# WeatherBoard_v1_1.net
KiCad netlist of a schematic drawn in EAGLE
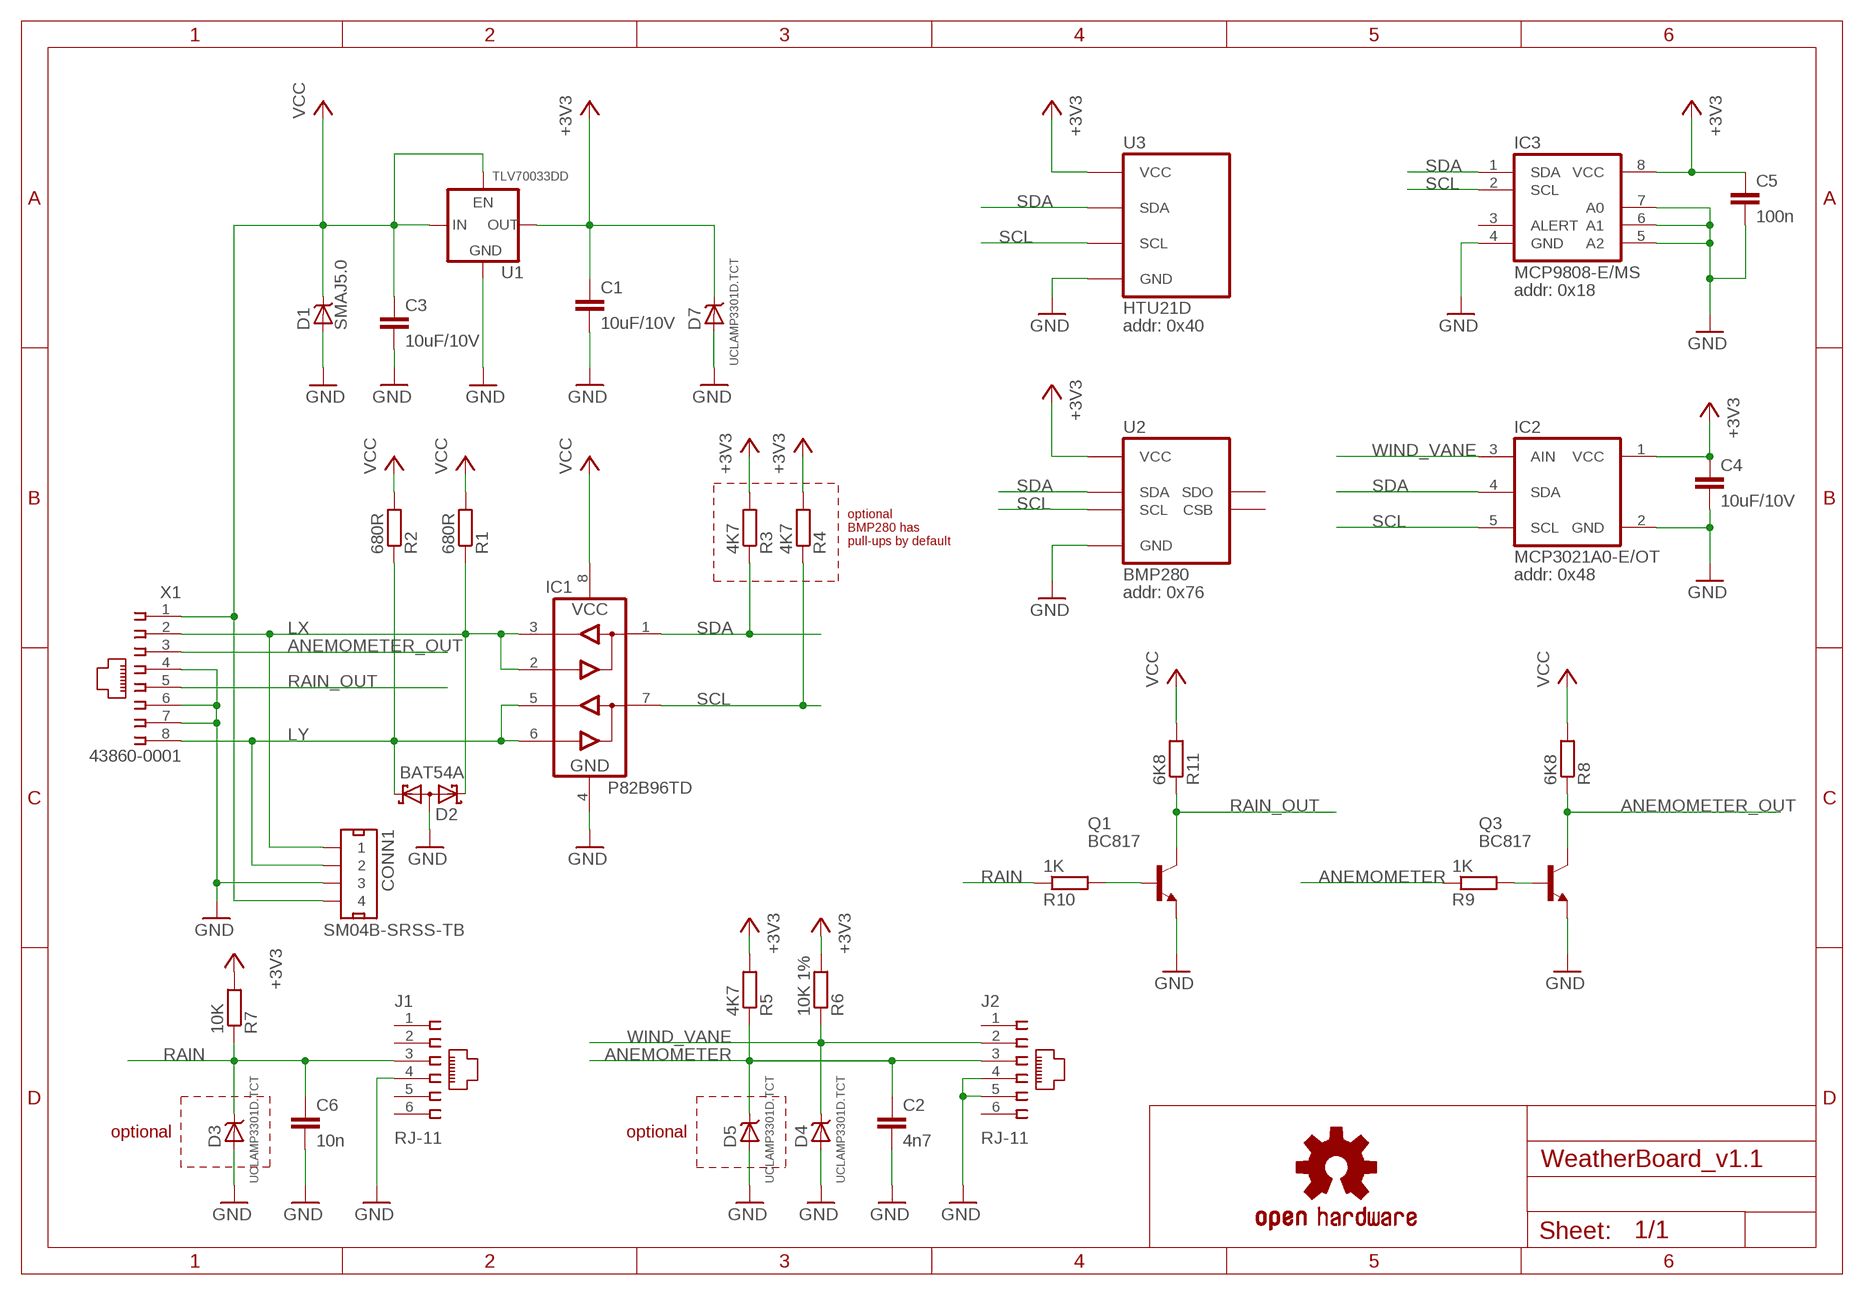
[diagram p0: schematic, sheet 1]

(export (version "E")
  (design (tool "Eeschema 10.0.6"))
  (components
    (comp (ref "C1")
      (value "10uF/10V")
      (footprint "eagle-import:C0805")
      (libsource (lib "eagle-import") (part "C-EUC0805"))
    )
    (comp (ref "C2")
      (value "4n7")
      (footprint "eagle-import:C0805")
      (libsource (lib "eagle-import") (part "C-EUC0805"))
    )
    (comp (ref "C3")
      (value "10uF/10V")
      (footprint "eagle-import:C0805")
      (libsource (lib "eagle-import") (part "C-EUC0805"))
    )
    (comp (ref "C4")
      (value "10uF/10V")
      (footprint "eagle-import:C0805")
      (libsource (lib "eagle-import") (part "C-EUC0805"))
    )
    (comp (ref "C5")
      (value "100n")
      (footprint "eagle-import:C0805")
      (libsource (lib "eagle-import") (part "C-EUC0805"))
    )
    (comp (ref "C6")
      (value "10n")
      (footprint "eagle-import:C0805")
      (libsource (lib "eagle-import") (part "C-EUC0805"))
    )
    (comp (ref "CONN1")
      (value "SM04B-SRSS-TB")
      (footprint "eagle-import:JST-SRSS-4-T")
      (libsource (lib "eagle-import") (part "?M04B-SRSS-TBS"))
    )
    (comp (ref "D1")
      (value "SMAJ5.0")
      (footprint "eagle-import:DO214AC")
      (libsource (lib "eagle-import") (part "SM?JA5.0"))
    )
    (comp (ref "D2")
      (value "BAT54A")
      (footprint "eagle-import:SOT23")
      (libsource (lib "eagle-import") (part "BAT54A"))
    )
    (comp (ref "D3")
      (value "UCLAMP3301D.TCT")
      (footprint "eagle-import:SOD323")
      (libsource (lib "eagle-import") (part "UCLAMP3301?.TCTD"))
    )
    (comp (ref "D4")
      (value "UCLAMP3301D.TCT")
      (footprint "eagle-import:SOD323")
      (libsource (lib "eagle-import") (part "UCLAMP3301?.TCTD"))
    )
    (comp (ref "D5")
      (value "UCLAMP3301D.TCT")
      (footprint "eagle-import:SOD323")
      (libsource (lib "eagle-import") (part "UCLAMP3301?.TCTD"))
    )
    (comp (ref "D7")
      (value "UCLAMP3301D.TCT")
      (footprint "eagle-import:SOD323")
      (libsource (lib "eagle-import") (part "UCLAMP3301?.TCTD"))
    )
    (comp (ref "IC1")
      (value "P82B96TD")
      (footprint "eagle-import:SO08")
      (libsource (lib "eagle-import") (part "P82B96?TD"))
    )
    (comp (ref "IC2")
      (value "MCP3021A0-E/OT")
      (footprint "eagle-import:SOT23-5")
      (libsource (lib "eagle-import") (part "MCP3021-E/?OTA0"))
    )
    (comp (ref "IC3")
      (value "MCP9808-E/MS")
      (footprint "eagle-import:MSOP8")
      (libsource (lib "eagle-import") (part "MCP9808-E/?MS"))
    )
    (comp (ref "J1")
      (value "RJ-11")
      (footprint "eagle-import:615006138421")
      (libsource (lib "eagle-import") (part "RJ-11"))
    )
    (comp (ref "J2")
      (value "RJ-11")
      (footprint "eagle-import:615006138421")
      (libsource (lib "eagle-import") (part "RJ-11"))
    )
    (comp (ref "LOGO1")
      (value "OSHW-LOGOM-COPPER")
      (footprint "eagle-import:OSHW-LOGO-M_COPPER")
      (libsource (lib "eagle-import") (part "OSHW-LOGOM-COPPER"))
    )
    (comp (ref "Q1")
      (value "BC817")
      (footprint "eagle-import:SOT23-BEC")
      (libsource (lib "eagle-import") (part "BC817SMD-40"))
    )
    (comp (ref "Q3")
      (value "BC817")
      (footprint "eagle-import:SOT23-BEC")
      (libsource (lib "eagle-import") (part "BC817SMD-40"))
    )
    (comp (ref "R1")
      (value "680R")
      (footprint "eagle-import:R0805")
      (libsource (lib "eagle-import") (part "R-EU_R0805"))
    )
    (comp (ref "R2")
      (value "680R")
      (footprint "eagle-import:R0805")
      (libsource (lib "eagle-import") (part "R-EU_R0805"))
    )
    (comp (ref "R3")
      (value "4K7")
      (footprint "eagle-import:R0805")
      (libsource (lib "eagle-import") (part "R-EU_R0805"))
    )
    (comp (ref "R4")
      (value "4K7")
      (footprint "eagle-import:R0805")
      (libsource (lib "eagle-import") (part "R-EU_R0805"))
    )
    (comp (ref "R5")
      (value "4K7")
      (footprint "eagle-import:R0805")
      (libsource (lib "eagle-import") (part "R-EU_R0805"))
    )
    (comp (ref "R6")
      (value "10K 1%")
      (footprint "eagle-import:R0805")
      (libsource (lib "eagle-import") (part "R-EU_R0805"))
    )
    (comp (ref "R7")
      (value "10K")
      (footprint "eagle-import:R0805")
      (libsource (lib "eagle-import") (part "R-EU_R0805"))
    )
    (comp (ref "R8")
      (value "6K8")
      (footprint "eagle-import:R0805")
      (libsource (lib "eagle-import") (part "R-EU_R0805"))
    )
    (comp (ref "R9")
      (value "1K")
      (footprint "eagle-import:R0805")
      (libsource (lib "eagle-import") (part "R-EU_R0805"))
    )
    (comp (ref "R10")
      (value "1K")
      (footprint "eagle-import:R0805")
      (libsource (lib "eagle-import") (part "R-EU_R0805"))
    )
    (comp (ref "R11")
      (value "6K8")
      (footprint "eagle-import:R0805")
      (libsource (lib "eagle-import") (part "R-EU_R0805"))
    )
    (comp (ref "U1")
      (value "TLV70033DD")
      (footprint "eagle-import:SOT23-5")
      (libsource (lib "eagle-import") (part "TLV700DD33"))
    )
    (comp (ref "U2")
      (value "BMP280")
      (footprint "eagle-import:BM_280")
      (libsource (lib "eagle-import") (part "BM280P"))
    )
    (comp (ref "U3")
      (value "HTU21D")
      (footprint "eagle-import:HTU21D")
      (libsource (lib "eagle-import") (part "HTU21D"))
    )
    (comp (ref "X1")
      (value "43860-0001")
      (footprint "eagle-import:MX-43860-0001")
      (libsource (lib "eagle-import") (part "43860-0001"))
    )
  )
  (nets
    (net (code "1") (name "+3V3") (class "Default")
      (node (ref "C1") (pin "1") (pinfunction "1_1") (pintype "passive"))
      (node (ref "C4") (pin "1") (pinfunction "1_1") (pintype "passive"))
      (node (ref "C5") (pin "1") (pinfunction "1_1") (pintype "passive"))
      (node (ref "D7") (pin "C") (pinfunction "C_C") (pintype "passive"))
      (node (ref "IC2") (pin "1") (pinfunction "VCC_1") (pintype "power_in"))
      (node (ref "IC3") (pin "8") (pinfunction "VCC_8") (pintype "power_in"))
      (node (ref "R3") (pin "2") (pinfunction "2_2") (pintype "passive"))
      (node (ref "R4") (pin "2") (pinfunction "2_2") (pintype "passive"))
      (node (ref "R5") (pin "2") (pinfunction "2_2") (pintype "passive"))
      (node (ref "R6") (pin "2") (pinfunction "2_2") (pintype "passive"))
      (node (ref "R7") (pin "2") (pinfunction "2_2") (pintype "passive"))
      (node (ref "U1") (pin "5") (pinfunction "VOUT_5") (pintype "power_in"))
      (node (ref "U2") (pin "VCC") (pinfunction "VCC_VCC") (pintype "power_in"))
      (node (ref "U3") (pin "VCC") (pinfunction "VCC_VCC") (pintype "power_in"))
    )
    (net (code "2") (name "/ANEMOMETER") (class "Default")
      (node (ref "C2") (pin "1") (pinfunction "1_1") (pintype "passive"))
      (node (ref "D5") (pin "C") (pinfunction "C_C") (pintype "passive"))
      (node (ref "J2") (pin "3") (pinfunction "3_3") (pintype "passive"))
      (node (ref "R5") (pin "1") (pinfunction "1_1") (pintype "passive"))
      (node (ref "R9") (pin "1") (pinfunction "1_1") (pintype "passive"))
    )
    (net (code "3") (name "/ANEMOMETER_OUT") (class "Default")
      (node (ref "Q3") (pin "C") (pinfunction "C_C") (pintype "passive"))
      (node (ref "R8") (pin "1") (pinfunction "1_1") (pintype "passive"))
      (node (ref "X1") (pin "3") (pinfunction "3_3") (pintype "passive"))
    )
    (net (code "4") (name "/LX") (class "Default")
      (node (ref "CONN1") (pin "1") (pinfunction "1_1") (pintype "passive"))
      (node (ref "D2") (pin "2") (pinfunction "K2_2") (pintype "passive"))
      (node (ref "IC1") (pin "2") (pinfunction "RX_2") (pintype "open_collector"))
      (node (ref "IC1") (pin "3") (pinfunction "TX_3") (pintype "open_collector"))
      (node (ref "R1") (pin "1") (pinfunction "1_1") (pintype "passive"))
      (node (ref "X1") (pin "2") (pinfunction "2_2") (pintype "passive"))
    )
    (net (code "5") (name "/LY") (class "Default")
      (node (ref "CONN1") (pin "2") (pinfunction "2_2") (pintype "passive"))
      (node (ref "D2") (pin "1") (pinfunction "K1_1") (pintype "passive"))
      (node (ref "IC1") (pin "5") (pinfunction "TY_5") (pintype "open_collector"))
      (node (ref "IC1") (pin "6") (pinfunction "RY_6") (pintype "open_collector"))
      (node (ref "R2") (pin "1") (pinfunction "1_1") (pintype "passive"))
      (node (ref "X1") (pin "8") (pinfunction "8_8") (pintype "passive"))
    )
    (net (code "6") (name "/RAIN") (class "Default")
      (node (ref "C6") (pin "1") (pinfunction "1_1") (pintype "passive"))
      (node (ref "D3") (pin "C") (pinfunction "C_C") (pintype "passive"))
      (node (ref "J1") (pin "3") (pinfunction "3_3") (pintype "passive"))
      (node (ref "R10") (pin "1") (pinfunction "1_1") (pintype "passive"))
      (node (ref "R7") (pin "1") (pinfunction "1_1") (pintype "passive"))
    )
    (net (code "7") (name "/RAIN_OUT") (class "Default")
      (node (ref "Q1") (pin "C") (pinfunction "C_C") (pintype "passive"))
      (node (ref "R11") (pin "1") (pinfunction "1_1") (pintype "passive"))
      (node (ref "X1") (pin "5") (pinfunction "5_5") (pintype "passive"))
    )
    (net (code "8") (name "/SCL") (class "Default")
      (node (ref "IC1") (pin "7") (pinfunction "SY_7") (pintype "input"))
      (node (ref "IC2") (pin "5") (pinfunction "SCL_5") (pintype "input"))
      (node (ref "IC3") (pin "2") (pinfunction "SCL_2") (pintype "bidirectional"))
      (node (ref "R4") (pin "1") (pinfunction "1_1") (pintype "passive"))
      (node (ref "U2") (pin "SCL") (pinfunction "SCL_SCL") (pintype "bidirectional"))
      (node (ref "U3") (pin "SCL") (pinfunction "SCL_SCL") (pintype "bidirectional"))
    )
    (net (code "9") (name "/SDA") (class "Default")
      (node (ref "IC1") (pin "1") (pinfunction "SX_1") (pintype "input"))
      (node (ref "IC2") (pin "4") (pinfunction "SDA_4") (pintype "bidirectional"))
      (node (ref "IC3") (pin "1") (pinfunction "SDA_1") (pintype "bidirectional"))
      (node (ref "R3") (pin "1") (pinfunction "1_1") (pintype "passive"))
      (node (ref "U2") (pin "SDA") (pinfunction "SDA_SDA") (pintype "bidirectional"))
      (node (ref "U3") (pin "SDA") (pinfunction "SDA_SDA") (pintype "bidirectional"))
    )
    (net (code "10") (name "/WIND_VANE") (class "Default")
      (node (ref "D4") (pin "C") (pinfunction "C_C") (pintype "passive"))
      (node (ref "IC2") (pin "3") (pinfunction "AIN_3") (pintype "bidirectional"))
      (node (ref "J2") (pin "2") (pinfunction "2_2") (pintype "passive"))
      (node (ref "R6") (pin "1") (pinfunction "1_1") (pintype "passive"))
    )
    (net (code "11") (name "GND") (class "Default")
      (node (ref "C1") (pin "2") (pinfunction "2_2") (pintype "passive"))
      (node (ref "C2") (pin "2") (pinfunction "2_2") (pintype "passive"))
      (node (ref "C3") (pin "2") (pinfunction "2_2") (pintype "passive"))
      (node (ref "C4") (pin "2") (pinfunction "2_2") (pintype "passive"))
      (node (ref "C5") (pin "2") (pinfunction "2_2") (pintype "passive"))
      (node (ref "C6") (pin "2") (pinfunction "2_2") (pintype "passive"))
      (node (ref "CONN1") (pin "3") (pinfunction "3_3") (pintype "passive"))
      (node (ref "D1") (pin "A") (pinfunction "A_A") (pintype "passive"))
      (node (ref "D2") (pin "3") (pinfunction "AA_3") (pintype "passive"))
      (node (ref "D3") (pin "A") (pinfunction "A_A") (pintype "passive"))
      (node (ref "D4") (pin "A") (pinfunction "A_A") (pintype "passive"))
      (node (ref "D5") (pin "A") (pinfunction "A_A") (pintype "passive"))
      (node (ref "D7") (pin "A") (pinfunction "A_A") (pintype "passive"))
      (node (ref "IC1") (pin "4") (pinfunction "GND_4") (pintype "power_in"))
      (node (ref "IC2") (pin "2") (pinfunction "GND_2") (pintype "power_in"))
      (node (ref "IC3") (pin "4") (pinfunction "GND_4") (pintype "power_in"))
      (node (ref "IC3") (pin "5") (pinfunction "A2_5") (pintype "input"))
      (node (ref "IC3") (pin "6") (pinfunction "A1_6") (pintype "input"))
      (node (ref "IC3") (pin "7") (pinfunction "A0_7") (pintype "input"))
      (node (ref "J1") (pin "4") (pinfunction "4_4") (pintype "passive"))
      (node (ref "J2") (pin "4") (pinfunction "4_4") (pintype "passive"))
      (node (ref "J2") (pin "5") (pinfunction "5_5") (pintype "passive"))
      (node (ref "Q1") (pin "E") (pinfunction "E_E") (pintype "passive"))
      (node (ref "Q3") (pin "E") (pinfunction "E_E") (pintype "passive"))
      (node (ref "U1") (pin "2") (pinfunction "GND_2") (pintype "power_in"))
      (node (ref "U2") (pin "GND") (pinfunction "GND_GND") (pintype "power_in"))
      (node (ref "U3") (pin "GND") (pinfunction "GND_GND") (pintype "power_in"))
      (node (ref "X1") (pin "4") (pinfunction "4_4") (pintype "passive"))
      (node (ref "X1") (pin "6") (pinfunction "6_6") (pintype "passive"))
      (node (ref "X1") (pin "7") (pinfunction "7_7") (pintype "passive"))
    )
    (net (code "12") (name "Net-(Q1-PadB)") (class "Default")
      (node (ref "Q1") (pin "B") (pinfunction "B_B") (pintype "passive"))
      (node (ref "R10") (pin "2") (pinfunction "2_2") (pintype "passive"))
    )
    (net (code "13") (name "Net-(Q3-PadB)") (class "Default")
      (node (ref "Q3") (pin "B") (pinfunction "B_B") (pintype "passive"))
      (node (ref "R9") (pin "2") (pinfunction "2_2") (pintype "passive"))
    )
    (net (code "14") (name "VCC") (class "Default")
      (node (ref "C3") (pin "1") (pinfunction "1_1") (pintype "passive"))
      (node (ref "CONN1") (pin "4") (pinfunction "4_4") (pintype "passive"))
      (node (ref "D1") (pin "C") (pinfunction "C_C") (pintype "passive"))
      (node (ref "IC1") (pin "8") (pinfunction "VCC_8") (pintype "power_in"))
      (node (ref "R1") (pin "2") (pinfunction "2_2") (pintype "passive"))
      (node (ref "R11") (pin "2") (pinfunction "2_2") (pintype "passive"))
      (node (ref "R2") (pin "2") (pinfunction "2_2") (pintype "passive"))
      (node (ref "R8") (pin "2") (pinfunction "2_2") (pintype "passive"))
      (node (ref "U1") (pin "1") (pinfunction "VIN_1") (pintype "power_in"))
      (node (ref "U1") (pin "3") (pinfunction "EN_3") (pintype "input"))
      (node (ref "X1") (pin "1") (pinfunction "1_1") (pintype "passive"))
    )
    (net (code "15") (name "unconnected-(CONN1-PAD1-PadNC2)") (class "Default")
      (node (ref "CONN1") (pin "NC2") (pinfunction "PAD1_NC2") (pintype "no_connect"))
    )
    (net (code "16") (name "unconnected-(CONN1-PAD2-PadNC1)") (class "Default")
      (node (ref "CONN1") (pin "NC1") (pinfunction "PAD2_NC1") (pintype "no_connect"))
    )
    (net (code "17") (name "unconnected-(IC3-ALERT-Pad3)") (class "Default")
      (node (ref "IC3") (pin "3") (pinfunction "ALERT_3") (pintype "open_collector"))
    )
    (net (code "18") (name "unconnected-(J1-Pad1)") (class "Default")
      (node (ref "J1") (pin "1") (pinfunction "1_1") (pintype "passive"))
    )
    (net (code "19") (name "unconnected-(J1-Pad2)") (class "Default")
      (node (ref "J1") (pin "2") (pinfunction "2_2") (pintype "passive"))
    )
    (net (code "20") (name "unconnected-(J1-Pad5)") (class "Default")
      (node (ref "J1") (pin "5") (pinfunction "5_5") (pintype "passive"))
    )
    (net (code "21") (name "unconnected-(J1-Pad6)") (class "Default")
      (node (ref "J1") (pin "6") (pinfunction "6_6") (pintype "passive"))
    )
    (net (code "22") (name "unconnected-(J2-Pad1)") (class "Default")
      (node (ref "J2") (pin "1") (pinfunction "1_1") (pintype "passive"))
    )
    (net (code "23") (name "unconnected-(J2-Pad6)") (class "Default")
      (node (ref "J2") (pin "6") (pinfunction "6_6") (pintype "passive"))
    )
    (net (code "24") (name "unconnected-(U2-PadCSB)") (class "Default")
      (node (ref "U2") (pin "CSB") (pinfunction "CSB_CSB") (pintype "bidirectional"))
    )
    (net (code "25") (name "unconnected-(U2-PadSDO)") (class "Default")
      (node (ref "U2") (pin "SDO") (pinfunction "SDO_SDO") (pintype "bidirectional"))
    )
  )
)
